# SilentStepStick-TMC2208_v20.net
KiCad netlist of a schematic drawn in EAGLE
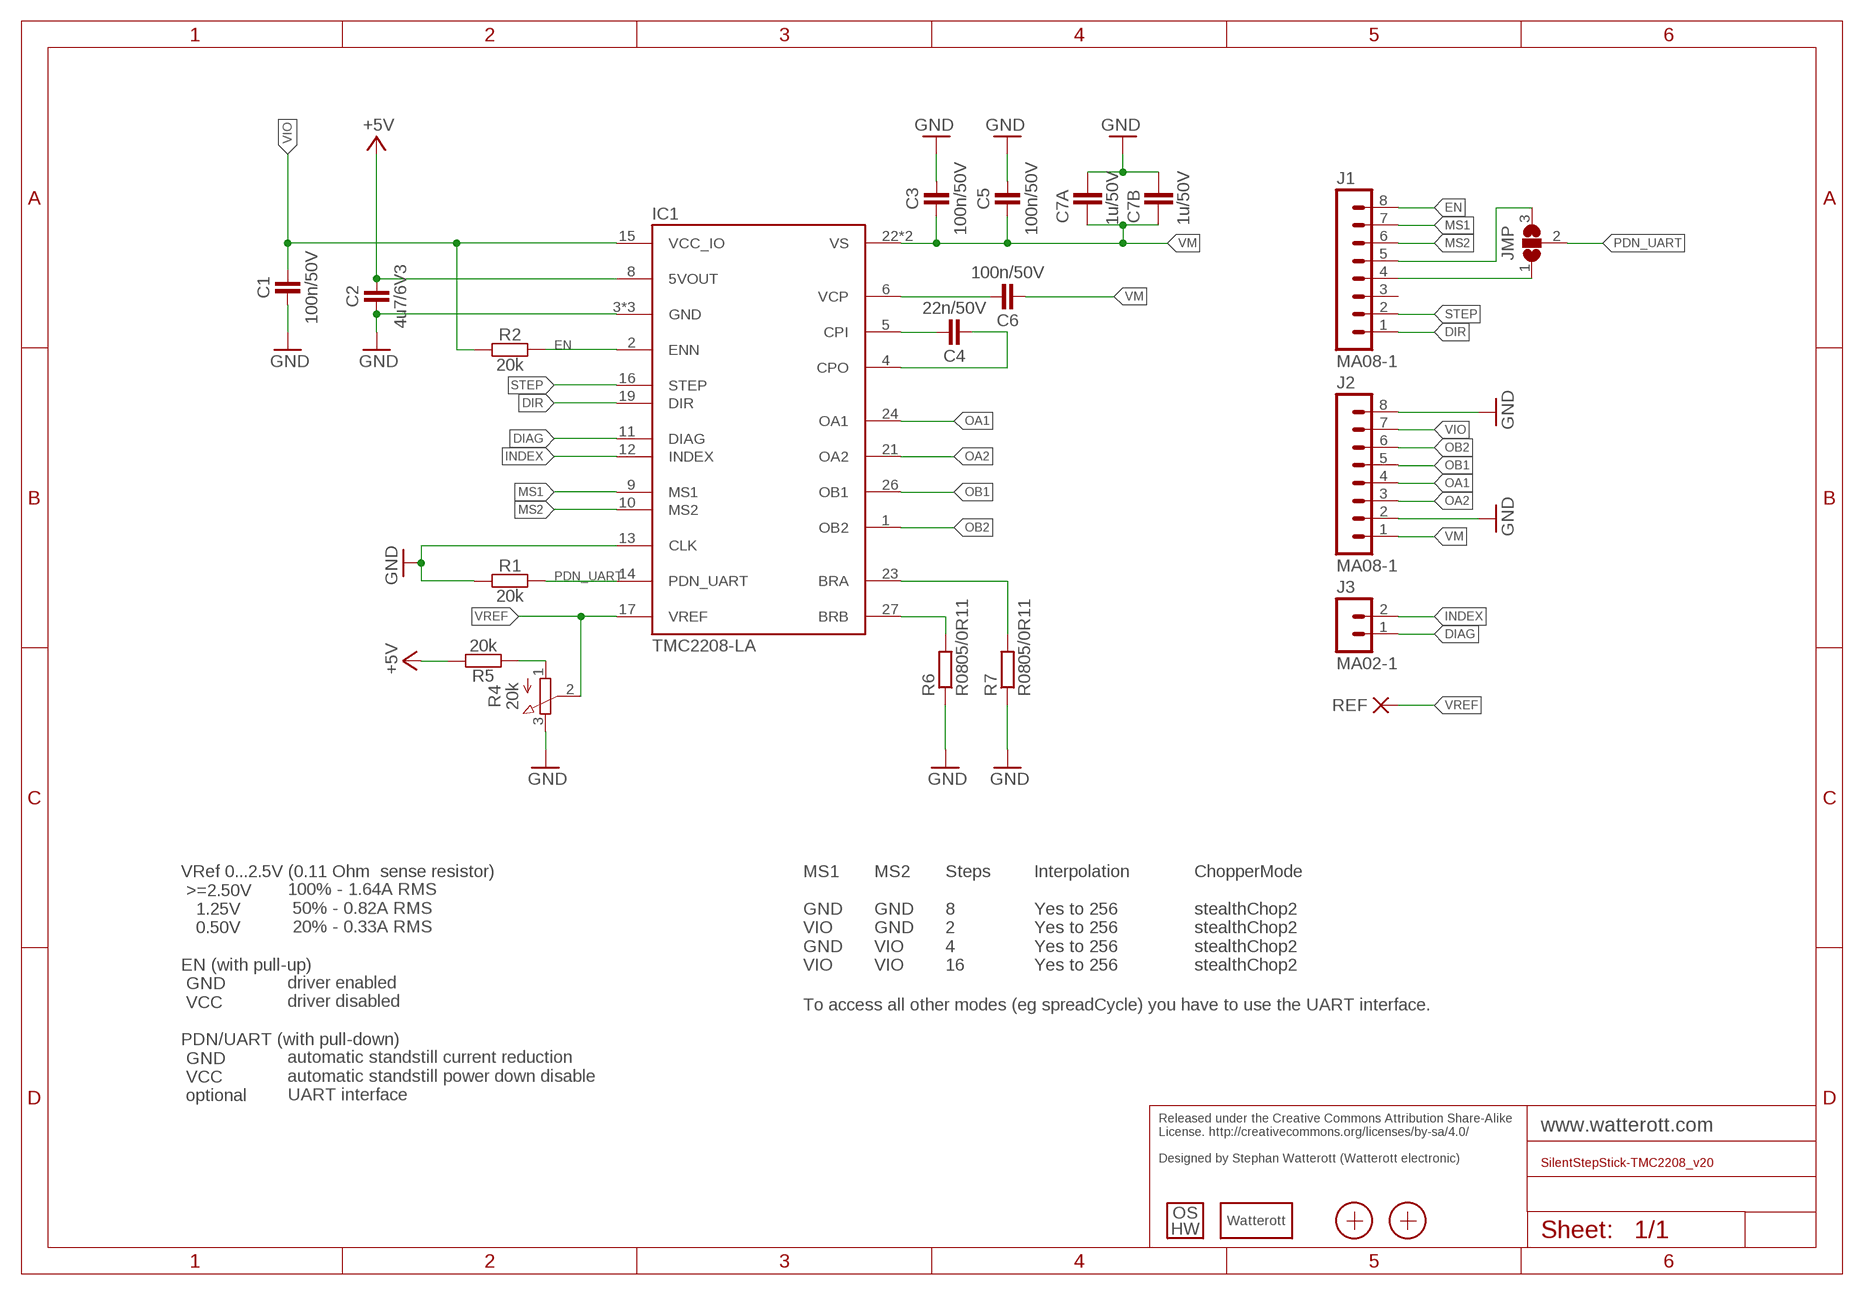
[diagram p0: schematic, sheet 1]

(export (version "E")
  (design (tool "Eeschema 10.0.6"))
  (components
    (comp (ref "C1")
      (value "100n/50V")
      (footprint "eagle-import:C0402")
      (libsource (lib "eagle-import") (part "CAPACITOR-0402"))
    )
    (comp (ref "C2")
      (value "4u7/6V3")
      (footprint "eagle-import:C0402")
      (libsource (lib "eagle-import") (part "CAPACITOR-0402"))
    )
    (comp (ref "C3")
      (value "100n/50V")
      (footprint "eagle-import:C0402")
      (libsource (lib "eagle-import") (part "CAPACITOR-0402"))
    )
    (comp (ref "C4")
      (value "22n/50V")
      (footprint "eagle-import:C0402")
      (libsource (lib "eagle-import") (part "CAPACITOR-0402"))
    )
    (comp (ref "C5")
      (value "100n/50V")
      (footprint "eagle-import:C0402")
      (libsource (lib "eagle-import") (part "CAPACITOR-0402"))
    )
    (comp (ref "C6")
      (value "100n/50V")
      (footprint "eagle-import:C0402")
      (libsource (lib "eagle-import") (part "CAPACITOR-0402"))
    )
    (comp (ref "C7A")
      (value "1u/50V")
      (footprint "eagle-import:C0805")
      (libsource (lib "eagle-import") (part "C-EUC0805"))
    )
    (comp (ref "C7B")
      (value "1u/50V")
      (footprint "eagle-import:C1206")
      (libsource (lib "eagle-import") (part "C-EUC1206"))
    )
    (comp (ref "IC1")
      (value "TMC2208-LA")
      (footprint "eagle-import:QFN28-PAD")
      (libsource (lib "eagle-import") (part "TMC2208-LA"))
    )
    (comp (ref "J1")
      (value "MA08-1")
      (footprint "eagle-import:MA08-1")
      (libsource (lib "eagle-import") (part "MA08-1"))
    )
    (comp (ref "J2")
      (value "MA08-1")
      (footprint "eagle-import:MA08-1")
      (libsource (lib "eagle-import") (part "MA08-1"))
    )
    (comp (ref "J3")
      (value "MA02-1")
      (footprint "eagle-import:MA02-1")
      (libsource (lib "eagle-import") (part "MA02-1"))
    )
    (comp (ref "JMP")
      (value "JUMPER3-0402-NC")
      (footprint "eagle-import:JUMPER3-0402_NC")
      (libsource (lib "eagle-import") (part "JUMPER3-0402-NC"))
    )
    (comp (ref "LOGO3")
      (value "LOGO_SPARK-2")
      (footprint "eagle-import:SPARK_2MM")
      (libsource (lib "eagle-import") (part "LOGO_SPARK-2"))
    )
    (comp (ref "LOGO4")
      (value "LOGO_OSHW-2")
      (footprint "eagle-import:OSHW_2MM")
      (libsource (lib "eagle-import") (part "LOGO_OSHW-2"))
    )
    (comp (ref "R1")
      (value "20k")
      (footprint "eagle-import:C0402")
      (libsource (lib "eagle-import") (part "RESISTOR-0402"))
    )
    (comp (ref "R2")
      (value "20k")
      (footprint "eagle-import:C0402")
      (libsource (lib "eagle-import") (part "RESISTOR-0402"))
    )
    (comp (ref "R4")
      (value "20k")
      (footprint "eagle-import:POT_EVM3R")
      (libsource (lib "eagle-import") (part "POT-EVM3R"))
    )
    (comp (ref "R5")
      (value "20k")
      (footprint "eagle-import:C0402")
      (libsource (lib "eagle-import") (part "RESISTOR-0402"))
    )
    (comp (ref "R6")
      (value "R0805/0R11")
      (footprint "eagle-import:M0805")
      (libsource (lib "eagle-import") (part "R-EU_M0805"))
    )
    (comp (ref "R7")
      (value "R0805/0R11")
      (footprint "eagle-import:M0805")
      (libsource (lib "eagle-import") (part "R-EU_M0805"))
    )
    (comp (ref "REF")
      (value "PAD-0.6-1.1")
      (footprint "eagle-import:PAD-0.6-1.1")
      (libsource (lib "eagle-import") (part "PAD-0.6-1.1"))
    )
    (comp (ref "X1")
      (value "PASSER-04")
      (footprint "eagle-import:PASSER_04MM")
      (libsource (lib "eagle-import") (part "PASSER-04"))
    )
    (comp (ref "X2")
      (value "PASSER-04")
      (footprint "eagle-import:PASSER_04MM")
      (libsource (lib "eagle-import") (part "PASSER-04"))
    )
  )
  (nets
    (net (code "1") (name "+5V") (class "Default")
      (node (ref "C2") (pin "2") (pinfunction "2_2") (pintype "passive"))
      (node (ref "IC1") (pin "8") (pinfunction "5VOUT_8") (pintype "power_in"))
      (node (ref "R5") (pin "2") (pinfunction "2_2") (pintype "passive"))
    )
    (net (code "2") (name "DIAG") (class "Default")
      (node (ref "IC1") (pin "11") (pinfunction "DIAG_11") (pintype "bidirectional"))
      (node (ref "J3") (pin "1") (pinfunction "1_1") (pintype "passive"))
    )
    (net (code "3") (name "DIR") (class "Default")
      (node (ref "IC1") (pin "19") (pinfunction "DIR_19") (pintype "bidirectional"))
      (node (ref "J1") (pin "1") (pinfunction "1_1") (pintype "passive"))
    )
    (net (code "4") (name "EN") (class "Default")
      (node (ref "IC1") (pin "2") (pinfunction "ENN_2") (pintype "bidirectional"))
      (node (ref "J1") (pin "8") (pinfunction "8_8") (pintype "passive"))
      (node (ref "R2") (pin "2") (pinfunction "2_2") (pintype "passive"))
    )
    (net (code "5") (name "GND") (class "Default")
      (node (ref "C1") (pin "1") (pinfunction "1_1") (pintype "passive"))
      (node (ref "C2") (pin "1") (pinfunction "1_1") (pintype "passive"))
      (node (ref "C3") (pin "2") (pinfunction "2_2") (pintype "passive"))
      (node (ref "C5") (pin "2") (pinfunction "2_2") (pintype "passive"))
      (node (ref "C7A") (pin "2") (pinfunction "2_2") (pintype "passive"))
      (node (ref "C7B") (pin "2") (pinfunction "2_2") (pintype "passive"))
      (node (ref "IC1") (pin "13") (pinfunction "CLK_13") (pintype "bidirectional"))
      (node (ref "IC1") (pin "18") (pinfunction "GND_18") (pintype "power_in"))
      (node (ref "IC1") (pin "3") (pinfunction "GND_3") (pintype "power_in"))
      (node (ref "IC1") (pin "TP") (pinfunction "GND_TP") (pintype "power_in"))
      (node (ref "J2") (pin "2") (pinfunction "2_2") (pintype "passive"))
      (node (ref "J2") (pin "8") (pinfunction "8_8") (pintype "passive"))
      (node (ref "R1") (pin "1") (pinfunction "1_1") (pintype "passive"))
      (node (ref "R4") (pin "3") (pinfunction "E_3") (pintype "passive"))
      (node (ref "R6") (pin "1") (pinfunction "1_1") (pintype "passive"))
      (node (ref "R7") (pin "1") (pinfunction "1_1") (pintype "passive"))
    )
    (net (code "6") (name "INDEX") (class "Default")
      (node (ref "IC1") (pin "12") (pinfunction "INDEX_12") (pintype "bidirectional"))
      (node (ref "J3") (pin "2") (pinfunction "2_2") (pintype "passive"))
    )
    (net (code "7") (name "MS1") (class "Default")
      (node (ref "IC1") (pin "9") (pinfunction "MS1_9") (pintype "bidirectional"))
      (node (ref "J1") (pin "7") (pinfunction "7_7") (pintype "passive"))
    )
    (net (code "8") (name "MS2") (class "Default")
      (node (ref "IC1") (pin "10") (pinfunction "MS2_10") (pintype "bidirectional"))
      (node (ref "J1") (pin "6") (pinfunction "6_6") (pintype "passive"))
    )
    (net (code "9") (name "Net-(IC1-BRA)") (class "Default")
      (node (ref "IC1") (pin "23") (pinfunction "BRA_23") (pintype "output"))
      (node (ref "R7") (pin "2") (pinfunction "2_2") (pintype "passive"))
    )
    (net (code "10") (name "Net-(IC1-BRB)") (class "Default")
      (node (ref "IC1") (pin "27") (pinfunction "BRB_27") (pintype "output"))
      (node (ref "R6") (pin "2") (pinfunction "2_2") (pintype "passive"))
    )
    (net (code "11") (name "Net-(IC1-CPI)") (class "Default")
      (node (ref "C4") (pin "2") (pinfunction "2_2") (pintype "passive"))
      (node (ref "IC1") (pin "5") (pinfunction "CPI_5") (pintype "passive"))
    )
    (net (code "12") (name "Net-(IC1-CPO)") (class "Default")
      (node (ref "C4") (pin "1") (pinfunction "1_1") (pintype "passive"))
      (node (ref "IC1") (pin "4") (pinfunction "CPO_4") (pintype "passive"))
    )
    (net (code "13") (name "Net-(IC1-VCP)") (class "Default")
      (node (ref "C6") (pin "2") (pinfunction "2_2") (pintype "passive"))
      (node (ref "IC1") (pin "6") (pinfunction "VCP_6") (pintype "passive"))
    )
    (net (code "14") (name "Net-(J1-Pad4)") (class "Default")
      (node (ref "J1") (pin "4") (pinfunction "4_4") (pintype "passive"))
      (node (ref "JMP") (pin "1") (pinfunction "1_1") (pintype "passive"))
    )
    (net (code "15") (name "Net-(J1-Pad5)") (class "Default")
      (node (ref "J1") (pin "5") (pinfunction "5_5") (pintype "passive"))
      (node (ref "JMP") (pin "3") (pinfunction "3_3") (pintype "passive"))
    )
    (net (code "16") (name "Net-(R4-A)") (class "Default")
      (node (ref "R4") (pin "1") (pinfunction "A_1") (pintype "passive"))
      (node (ref "R5") (pin "1") (pinfunction "1_1") (pintype "passive"))
    )
    (net (code "17") (name "OA1") (class "Default")
      (node (ref "IC1") (pin "24") (pinfunction "OA1_24") (pintype "output"))
      (node (ref "J2") (pin "4") (pinfunction "4_4") (pintype "passive"))
    )
    (net (code "18") (name "OA2") (class "Default")
      (node (ref "IC1") (pin "21") (pinfunction "OA2_21") (pintype "output"))
      (node (ref "J2") (pin "3") (pinfunction "3_3") (pintype "passive"))
    )
    (net (code "19") (name "OB1") (class "Default")
      (node (ref "IC1") (pin "26") (pinfunction "OB1_26") (pintype "output"))
      (node (ref "J2") (pin "5") (pinfunction "5_5") (pintype "passive"))
    )
    (net (code "20") (name "OB2") (class "Default")
      (node (ref "IC1") (pin "1") (pinfunction "OB2_1") (pintype "output"))
      (node (ref "J2") (pin "6") (pinfunction "6_6") (pintype "passive"))
    )
    (net (code "21") (name "PDN_UART") (class "Default")
      (node (ref "IC1") (pin "14") (pinfunction "PDN_UART_14") (pintype "bidirectional"))
      (node (ref "JMP") (pin "2") (pinfunction "2_2") (pintype "passive"))
      (node (ref "R1") (pin "2") (pinfunction "2_2") (pintype "passive"))
    )
    (net (code "22") (name "STEP") (class "Default")
      (node (ref "IC1") (pin "16") (pinfunction "STEP_16") (pintype "bidirectional"))
      (node (ref "J1") (pin "2") (pinfunction "2_2") (pintype "passive"))
    )
    (net (code "23") (name "VIO") (class "Default")
      (node (ref "C1") (pin "2") (pinfunction "2_2") (pintype "passive"))
      (node (ref "IC1") (pin "15") (pinfunction "VCC_IO_15") (pintype "power_in"))
      (node (ref "J2") (pin "7") (pinfunction "7_7") (pintype "passive"))
      (node (ref "R2") (pin "1") (pinfunction "1_1") (pintype "passive"))
    )
    (net (code "24") (name "VM") (class "Default")
      (node (ref "C3") (pin "1") (pinfunction "1_1") (pintype "passive"))
      (node (ref "C5") (pin "1") (pinfunction "1_1") (pintype "passive"))
      (node (ref "C6") (pin "1") (pinfunction "1_1") (pintype "passive"))
      (node (ref "C7A") (pin "1") (pinfunction "1_1") (pintype "passive"))
      (node (ref "C7B") (pin "1") (pinfunction "1_1") (pintype "passive"))
      (node (ref "IC1") (pin "22") (pinfunction "VS_22") (pintype "power_in"))
      (node (ref "IC1") (pin "28") (pinfunction "VS_28") (pintype "power_in"))
      (node (ref "J2") (pin "1") (pinfunction "1_1") (pintype "passive"))
    )
    (net (code "25") (name "VREF") (class "Default")
      (node (ref "IC1") (pin "17") (pinfunction "VREF_17") (pintype "passive"))
      (node (ref "R4") (pin "2") (pinfunction "S_2") (pintype "passive"))
      (node (ref "REF") (pin "1") (pinfunction "P_1") (pintype "passive"))
    )
    (net (code "26") (name "unconnected-(J1-Pad3)") (class "Default")
      (node (ref "J1") (pin "3") (pinfunction "3_3") (pintype "passive"))
    )
  )
)
